# STM32.net
KiCad netlist of a schematic drawn in Altium Designer
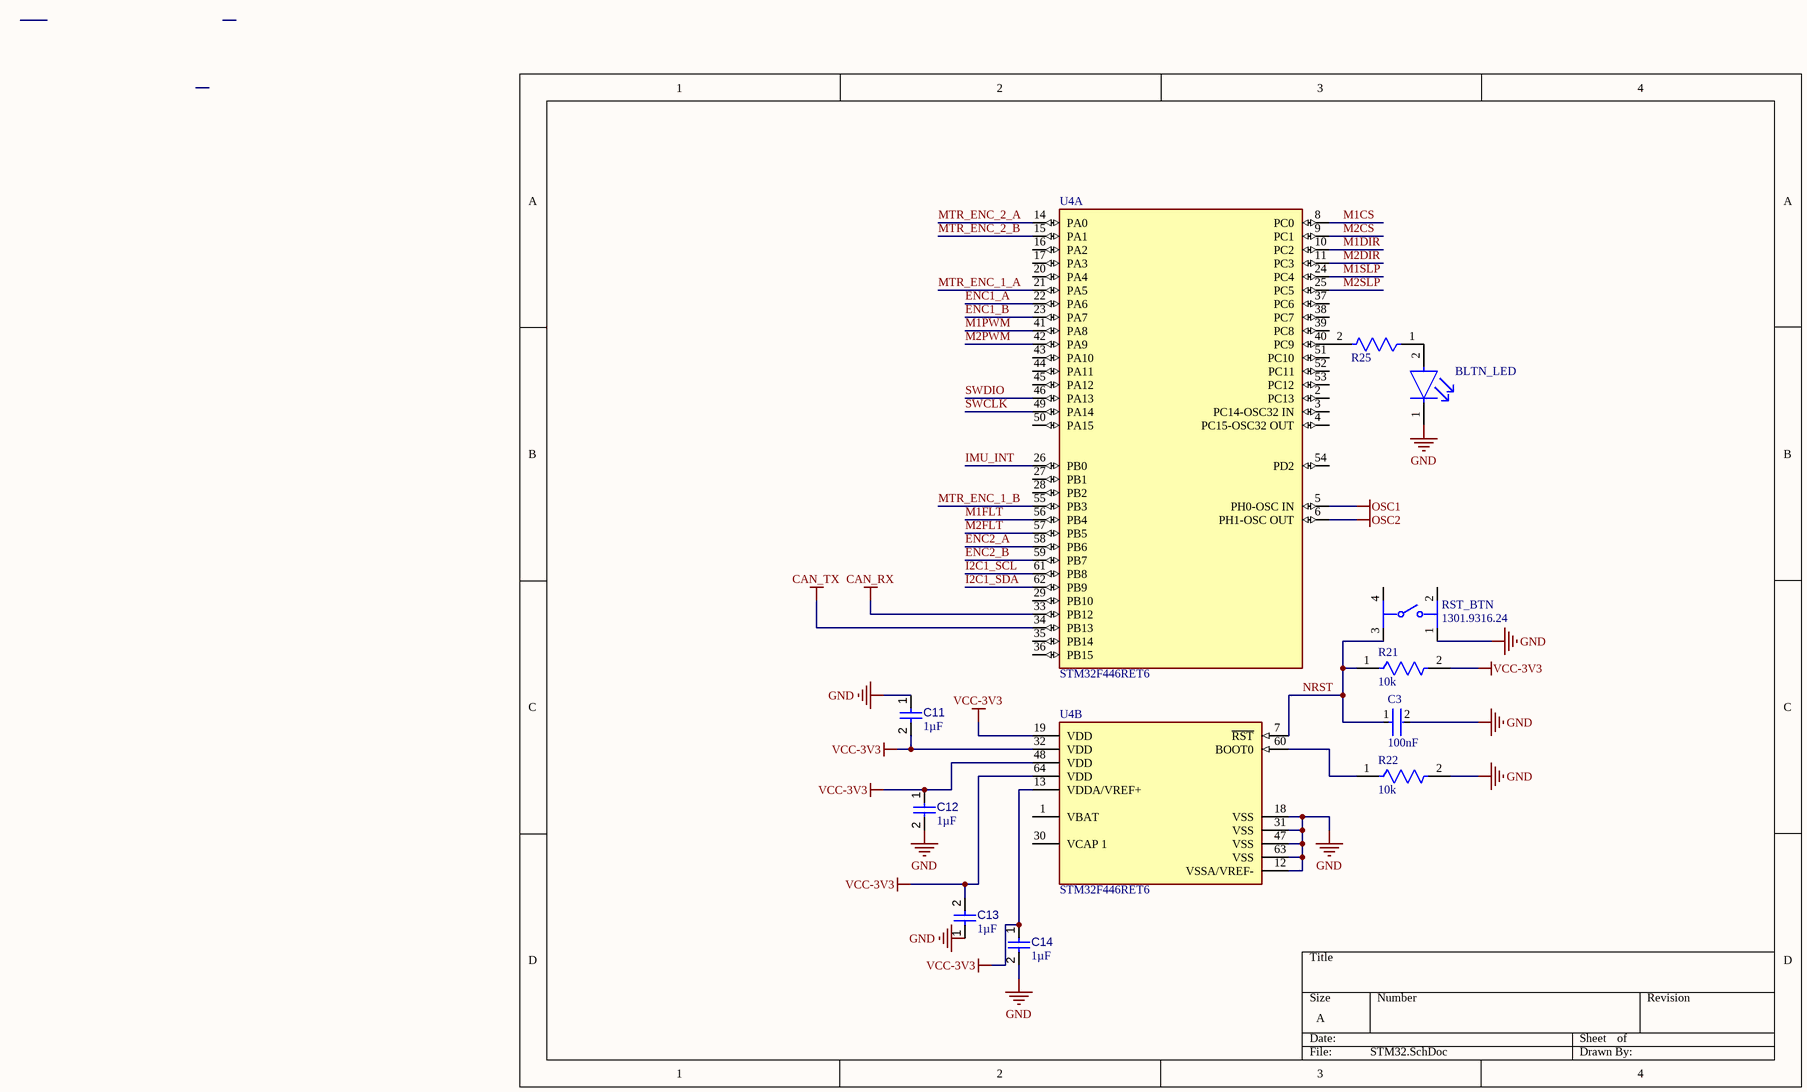
[diagram p0: STM32.SchDoc]

(export (version "E")
  (design (tool "Eeschema 10.0.6"))
  (components
    (comp (ref "BLTN_LED")
      (value "APHCM2012CGCK-F01")
      (footprint "FP-APHCM2012CGCK-F01-MFG")
      (description "LED GREEN CLEAR CHIP SMD")
      (libsource (lib "Altium Content Vault") (part "8706943c75ba83719d021d2fdc84c58"))
    )
    (comp (ref "C3")
      (value "100nF")
      (footprint "FP-0402B104K160CT-IPC_C")
      (description "CAP CER 0.1UF 16V X7R 0402")
      (fields (field (name "TOLERANCE") "10%"))
      (libsource (lib "Altium Content Vault") (part "b4654b650e69147ec39a6b967a45e02"))
    )
    (comp (ref "C11")
      (value "1µF")
      (footprint "CAPC0603(1608)100_L")
      (description "Chip Capacitor, 1µF +/-40%, 50V, 0603, Thickness 1 mm")
      (fields (field (name "TOLERANCE") "10%") (field (name "Comment") "Capacitor 1µF +/-40% 50V 0603"))
      (libsource (lib "RUR") (part "CAP-NP-2"))
    )
    (comp (ref "C12")
      (value "1µF")
      (footprint "CAPC0603(1608)100_L")
      (description "Chip Capacitor, 1µF +/-40%, 50V, 0603, Thickness 1 mm")
      (fields (field (name "TOLERANCE") "10%") (field (name "Comment") "Capacitor 1µF +/-40% 50V 0603"))
      (libsource (lib "RUR") (part "CAP-NP-2"))
    )
    (comp (ref "C13")
      (value "1µF")
      (footprint "CAPC0603(1608)100_L")
      (description "Chip Capacitor, 1µF +/-40%, 50V, 0603, Thickness 1 mm")
      (fields (field (name "TOLERANCE") "10%") (field (name "Comment") "Capacitor 1µF +/-40% 50V 0603"))
      (libsource (lib "RUR") (part "CAP-NP-2"))
    )
    (comp (ref "C14")
      (value "1µF")
      (footprint "CAPC0603(1608)100_L")
      (description "Chip Capacitor, 1µF +/-40%, 50V, 0603, Thickness 1 mm")
      (fields (field (name "TOLERANCE") "10%") (field (name "Comment") "Capacitor 1µF +/-40% 50V 0603"))
      (libsource (lib "RUR") (part "CAP-NP-2"))
    )
    (comp (ref "R21")
      (value "10k")
      (footprint "FP-RC0603-0_55-IPC_C")
      (description "RES 10K OHM 1% 1/10W 0603")
      (fields (field (name "TOLERANCE") "1%"))
      (libsource (lib "Altium Content Vault") (part "1029c3af85768c4190bb7ad29bc67b5"))
    )
    (comp (ref "R22")
      (value "10k")
      (footprint "FP-RC0603-0_55-IPC_C")
      (description "RES 10K OHM 1% 1/10W 0603")
      (fields (field (name "TOLERANCE") "1%"))
      (libsource (lib "Altium Content Vault") (part "1029c3af85768c4190bb7ad29bc67b5"))
    )
    (comp (ref "R25")
      (value "AC0603FR-10470RL")
      (footprint "FP-AC0603-IPC_A")
      (description "RES 470Ω 1.00% 0.1W 0603")
      (fields (field (name "TOLERANCE") "1%"))
      (libsource (lib "Altium Content Vault") (part "1029c3af85768c4190bb7ad29bc67b5"))
    )
    (comp (ref "RST_BTN")
      (value "1301.9316.24")
      (footprint "FP-1301_9316_24-MFG")
      (description "LSH 6X6 SHORT TRAVEL SWITCH 7.00")
      (libsource (lib "Altium Content Vault") (part "c0df99d12937e9d2da15afdedf14b17"))
    )
    (comp (ref "U4")
      (value "STM32F446RET6")
      (footprint "FP-LQFP64-5W-MFG")
      (description "IC MCU 32BIT 512KB FLASH 64LQFP")
      (fields
        (field (name "OCTOPART") "https://octopart.com/stm32f446ret6-stmicroelectronics-52642920")
        (field (name "MANUFACTURER") "ST")
      )
      (libsource (lib "Altium Content Vault") (part "ee11adc32c0ab33b933cccf4348c338"))
    )
  )
  (nets
    (net (code "1") (name "/ENC1_A") (class "Default")
      (node (ref "U4") (pin "22") (pinfunction "PA6_22") (pintype "bidirectional"))
    )
    (net (code "2") (name "/ENC1_B") (class "Default")
      (node (ref "U4") (pin "23") (pinfunction "PA7_23") (pintype "bidirectional"))
    )
    (net (code "3") (name "/ENC2_A") (class "Default")
      (node (ref "U4") (pin "58") (pinfunction "PB6_58") (pintype "bidirectional"))
    )
    (net (code "4") (name "/ENC2_B") (class "Default")
      (node (ref "U4") (pin "59") (pinfunction "PB7_59") (pintype "bidirectional"))
    )
    (net (code "5") (name "/I2C1_SCL") (class "Default")
      (node (ref "U4") (pin "61") (pinfunction "PB8_61") (pintype "bidirectional"))
    )
    (net (code "6") (name "/I2C1_SDA") (class "Default")
      (node (ref "U4") (pin "62") (pinfunction "PB9_62") (pintype "bidirectional"))
    )
    (net (code "7") (name "/IMU_INT") (class "Default")
      (node (ref "U4") (pin "26") (pinfunction "PB0_26") (pintype "bidirectional"))
    )
    (net (code "8") (name "/M1CS") (class "Default")
      (node (ref "U4") (pin "8") (pinfunction "PC0_8") (pintype "bidirectional"))
    )
    (net (code "9") (name "/M1DIR") (class "Default")
      (node (ref "U4") (pin "10") (pinfunction "PC2_10") (pintype "bidirectional"))
    )
    (net (code "10") (name "/M1FLT") (class "Default")
      (node (ref "U4") (pin "56") (pinfunction "PB4_56") (pintype "bidirectional"))
    )
    (net (code "11") (name "/M1PWM") (class "Default")
      (node (ref "U4") (pin "41") (pinfunction "PA8_41") (pintype "bidirectional"))
    )
    (net (code "12") (name "/M1SLP") (class "Default")
      (node (ref "U4") (pin "24") (pinfunction "PC4_24") (pintype "bidirectional"))
    )
    (net (code "13") (name "/M2CS") (class "Default")
      (node (ref "U4") (pin "9") (pinfunction "PC1_9") (pintype "bidirectional"))
    )
    (net (code "14") (name "/M2DIR") (class "Default")
      (node (ref "U4") (pin "11") (pinfunction "PC3_11") (pintype "bidirectional"))
    )
    (net (code "15") (name "/M2FLT") (class "Default")
      (node (ref "U4") (pin "57") (pinfunction "PB5_57") (pintype "bidirectional"))
    )
    (net (code "16") (name "/M2PWM") (class "Default")
      (node (ref "U4") (pin "42") (pinfunction "PA9_42") (pintype "bidirectional"))
    )
    (net (code "17") (name "/M2SLP") (class "Default")
      (node (ref "U4") (pin "25") (pinfunction "PC5_25") (pintype "bidirectional"))
    )
    (net (code "18") (name "/MTR_ENC_1_A") (class "Default")
      (node (ref "U4") (pin "21") (pinfunction "PA5_21") (pintype "bidirectional"))
    )
    (net (code "19") (name "/MTR_ENC_1_B") (class "Default")
      (node (ref "U4") (pin "55") (pinfunction "PB3_55") (pintype "bidirectional"))
    )
    (net (code "20") (name "/MTR_ENC_2_A") (class "Default")
      (node (ref "U4") (pin "14") (pinfunction "PA0_14") (pintype "bidirectional"))
    )
    (net (code "21") (name "/MTR_ENC_2_B") (class "Default")
      (node (ref "U4") (pin "15") (pinfunction "PA1_15") (pintype "bidirectional"))
    )
    (net (code "22") (name "/NRST") (class "Default")
      (node (ref "C3") (pin "1") (pinfunction "1_1") (pintype "passive"))
      (node (ref "R21") (pin "1") (pinfunction "1_1") (pintype "passive"))
      (node (ref "RST_BTN") (pin "3") (pinfunction "3_3") (pintype "passive"))
      (node (ref "U4") (pin "7") (pinfunction "~{RST}_7") (pintype "input"))
    )
    (net (code "23") (name "/SWCLK") (class "Default")
      (node (ref "U4") (pin "49") (pinfunction "PA14_49") (pintype "bidirectional"))
    )
    (net (code "24") (name "/SWDIO") (class "Default")
      (node (ref "U4") (pin "46") (pinfunction "PA13_46") (pintype "bidirectional"))
    )
    (net (code "25") (name "CAN_RX") (class "Default")
      (node (ref "U4") (pin "33") (pinfunction "PB12_33") (pintype "bidirectional"))
    )
    (net (code "26") (name "CAN_TX") (class "Default")
      (node (ref "U4") (pin "34") (pinfunction "PB13_34") (pintype "bidirectional"))
    )
    (net (code "27") (name "GND") (class "Default")
      (node (ref "BLTN_LED") (pin "1") (pinfunction "C_1") (pintype "passive"))
      (node (ref "C11") (pin "1") (pinfunction "1_1") (pintype "passive"))
      (node (ref "C12") (pin "2") (pinfunction "2_2") (pintype "passive"))
      (node (ref "C13") (pin "1") (pinfunction "1_1") (pintype "passive"))
      (node (ref "C14") (pin "2") (pinfunction "2_2") (pintype "passive"))
      (node (ref "C3") (pin "2") (pinfunction "2_2") (pintype "passive"))
      (node (ref "R22") (pin "2") (pinfunction "2_2") (pintype "passive"))
      (node (ref "RST_BTN") (pin "1") (pinfunction "1_1") (pintype "passive"))
      (node (ref "U4") (pin "12") (pinfunction "VSSA/VREF-_12") (pintype "power_in"))
      (node (ref "U4") (pin "18") (pinfunction "VSS_18") (pintype "power_in"))
      (node (ref "U4") (pin "31") (pinfunction "VSS_31") (pintype "power_in"))
      (node (ref "U4") (pin "47") (pinfunction "VSS_47") (pintype "power_in"))
      (node (ref "U4") (pin "63") (pinfunction "VSS_63") (pintype "power_in"))
    )
    (net (code "28") (name "Net-(BLTN_LED-A)") (class "Default")
      (node (ref "BLTN_LED") (pin "2") (pinfunction "A_2") (pintype "passive"))
      (node (ref "R25") (pin "1") (pinfunction "1_1") (pintype "passive"))
    )
    (net (code "29") (name "Net-(U4A-PC9)") (class "Default")
      (node (ref "R25") (pin "2") (pinfunction "2_2") (pintype "passive"))
      (node (ref "U4") (pin "40") (pinfunction "PC9_40") (pintype "bidirectional"))
    )
    (net (code "30") (name "Net-(U4B-BOOT0)") (class "Default")
      (node (ref "R22") (pin "1") (pinfunction "1_1") (pintype "passive"))
      (node (ref "U4") (pin "60") (pinfunction "BOOT0_60") (pintype "input"))
    )
    (net (code "31") (name "OSC1") (class "Default")
      (node (ref "U4") (pin "5") (pinfunction "PH0-OSC_IN_5") (pintype "bidirectional"))
    )
    (net (code "32") (name "OSC2") (class "Default")
      (node (ref "U4") (pin "6") (pinfunction "PH1-OSC_OUT_6") (pintype "bidirectional"))
    )
    (net (code "33") (name "VCC-3V3") (class "Default")
      (node (ref "C11") (pin "2") (pinfunction "2_2") (pintype "passive"))
      (node (ref "C12") (pin "1") (pinfunction "1_1") (pintype "passive"))
      (node (ref "C13") (pin "2") (pinfunction "2_2") (pintype "passive"))
      (node (ref "C14") (pin "1") (pinfunction "1_1") (pintype "passive"))
      (node (ref "R21") (pin "2") (pinfunction "2_2") (pintype "passive"))
      (node (ref "U4") (pin "13") (pinfunction "VDDA/VREF+_13") (pintype "power_in"))
      (node (ref "U4") (pin "19") (pinfunction "VDD_19") (pintype "power_in"))
      (node (ref "U4") (pin "32") (pinfunction "VDD_32") (pintype "power_in"))
      (node (ref "U4") (pin "48") (pinfunction "VDD_48") (pintype "power_in"))
      (node (ref "U4") (pin "64") (pinfunction "VDD_64") (pintype "power_in"))
    )
    (net (code "34") (name "unconnected-(RST_BTN-Pad2)") (class "Default")
      (node (ref "RST_BTN") (pin "2") (pinfunction "2_2") (pintype "passive"))
    )
    (net (code "35") (name "unconnected-(RST_BTN-Pad4)") (class "Default")
      (node (ref "RST_BTN") (pin "4") (pinfunction "4_4") (pintype "passive"))
    )
    (net (code "36") (name "unconnected-(U4A-PA2-Pad16)") (class "Default")
      (node (ref "U4") (pin "16") (pinfunction "PA2_16") (pintype "bidirectional"))
    )
    (net (code "37") (name "unconnected-(U4A-PA3-Pad17)") (class "Default")
      (node (ref "U4") (pin "17") (pinfunction "PA3_17") (pintype "bidirectional"))
    )
    (net (code "38") (name "unconnected-(U4A-PA4-Pad20)") (class "Default")
      (node (ref "U4") (pin "20") (pinfunction "PA4_20") (pintype "bidirectional"))
    )
    (net (code "39") (name "unconnected-(U4A-PA10-Pad43)") (class "Default")
      (node (ref "U4") (pin "43") (pinfunction "PA10_43") (pintype "bidirectional"))
    )
    (net (code "40") (name "unconnected-(U4A-PA11-Pad44)") (class "Default")
      (node (ref "U4") (pin "44") (pinfunction "PA11_44") (pintype "bidirectional"))
    )
    (net (code "41") (name "unconnected-(U4A-PA12-Pad45)") (class "Default")
      (node (ref "U4") (pin "45") (pinfunction "PA12_45") (pintype "bidirectional"))
    )
    (net (code "42") (name "unconnected-(U4A-PA15-Pad50)") (class "Default")
      (node (ref "U4") (pin "50") (pinfunction "PA15_50") (pintype "bidirectional"))
    )
    (net (code "43") (name "unconnected-(U4A-PB1-Pad27)") (class "Default")
      (node (ref "U4") (pin "27") (pinfunction "PB1_27") (pintype "bidirectional"))
    )
    (net (code "44") (name "unconnected-(U4A-PB2-Pad28)") (class "Default")
      (node (ref "U4") (pin "28") (pinfunction "PB2_28") (pintype "bidirectional"))
    )
    (net (code "45") (name "unconnected-(U4A-PB10-Pad29)") (class "Default")
      (node (ref "U4") (pin "29") (pinfunction "PB10_29") (pintype "bidirectional"))
    )
    (net (code "46") (name "unconnected-(U4A-PB14-Pad35)") (class "Default")
      (node (ref "U4") (pin "35") (pinfunction "PB14_35") (pintype "bidirectional"))
    )
    (net (code "47") (name "unconnected-(U4A-PB15-Pad36)") (class "Default")
      (node (ref "U4") (pin "36") (pinfunction "PB15_36") (pintype "bidirectional"))
    )
    (net (code "48") (name "unconnected-(U4A-PC6-Pad37)") (class "Default")
      (node (ref "U4") (pin "37") (pinfunction "PC6_37") (pintype "bidirectional"))
    )
    (net (code "49") (name "unconnected-(U4A-PC7-Pad38)") (class "Default")
      (node (ref "U4") (pin "38") (pinfunction "PC7_38") (pintype "bidirectional"))
    )
    (net (code "50") (name "unconnected-(U4A-PC8-Pad39)") (class "Default")
      (node (ref "U4") (pin "39") (pinfunction "PC8_39") (pintype "bidirectional"))
    )
    (net (code "51") (name "unconnected-(U4A-PC10-Pad51)") (class "Default")
      (node (ref "U4") (pin "51") (pinfunction "PC10_51") (pintype "bidirectional"))
    )
    (net (code "52") (name "unconnected-(U4A-PC11-Pad52)") (class "Default")
      (node (ref "U4") (pin "52") (pinfunction "PC11_52") (pintype "bidirectional"))
    )
    (net (code "53") (name "unconnected-(U4A-PC12-Pad53)") (class "Default")
      (node (ref "U4") (pin "53") (pinfunction "PC12_53") (pintype "bidirectional"))
    )
    (net (code "54") (name "unconnected-(U4A-PC13-Pad2)") (class "Default")
      (node (ref "U4") (pin "2") (pinfunction "PC13_2") (pintype "bidirectional"))
    )
    (net (code "55") (name "unconnected-(U4A-PC14-OSC32_IN-Pad3)") (class "Default")
      (node (ref "U4") (pin "3") (pinfunction "PC14-OSC32_IN_3") (pintype "bidirectional"))
    )
    (net (code "56") (name "unconnected-(U4A-PC15-OSC32_OUT-Pad4)") (class "Default")
      (node (ref "U4") (pin "4") (pinfunction "PC15-OSC32_OUT_4") (pintype "bidirectional"))
    )
    (net (code "57") (name "unconnected-(U4A-PD2-Pad54)") (class "Default")
      (node (ref "U4") (pin "54") (pinfunction "PD2_54") (pintype "bidirectional"))
    )
    (net (code "58") (name "unconnected-(U4B-VBAT-Pad1)") (class "Default")
      (node (ref "U4") (pin "1") (pinfunction "VBAT_1") (pintype "power_in"))
    )
    (net (code "59") (name "unconnected-(U4B-VCAP_1-Pad30)") (class "Default")
      (node (ref "U4") (pin "30") (pinfunction "VCAP_1_30") (pintype "power_in"))
    )
  )
)
